# expansion_module_BT_RN42.net
KiCad netlist of a schematic drawn in EAGLE
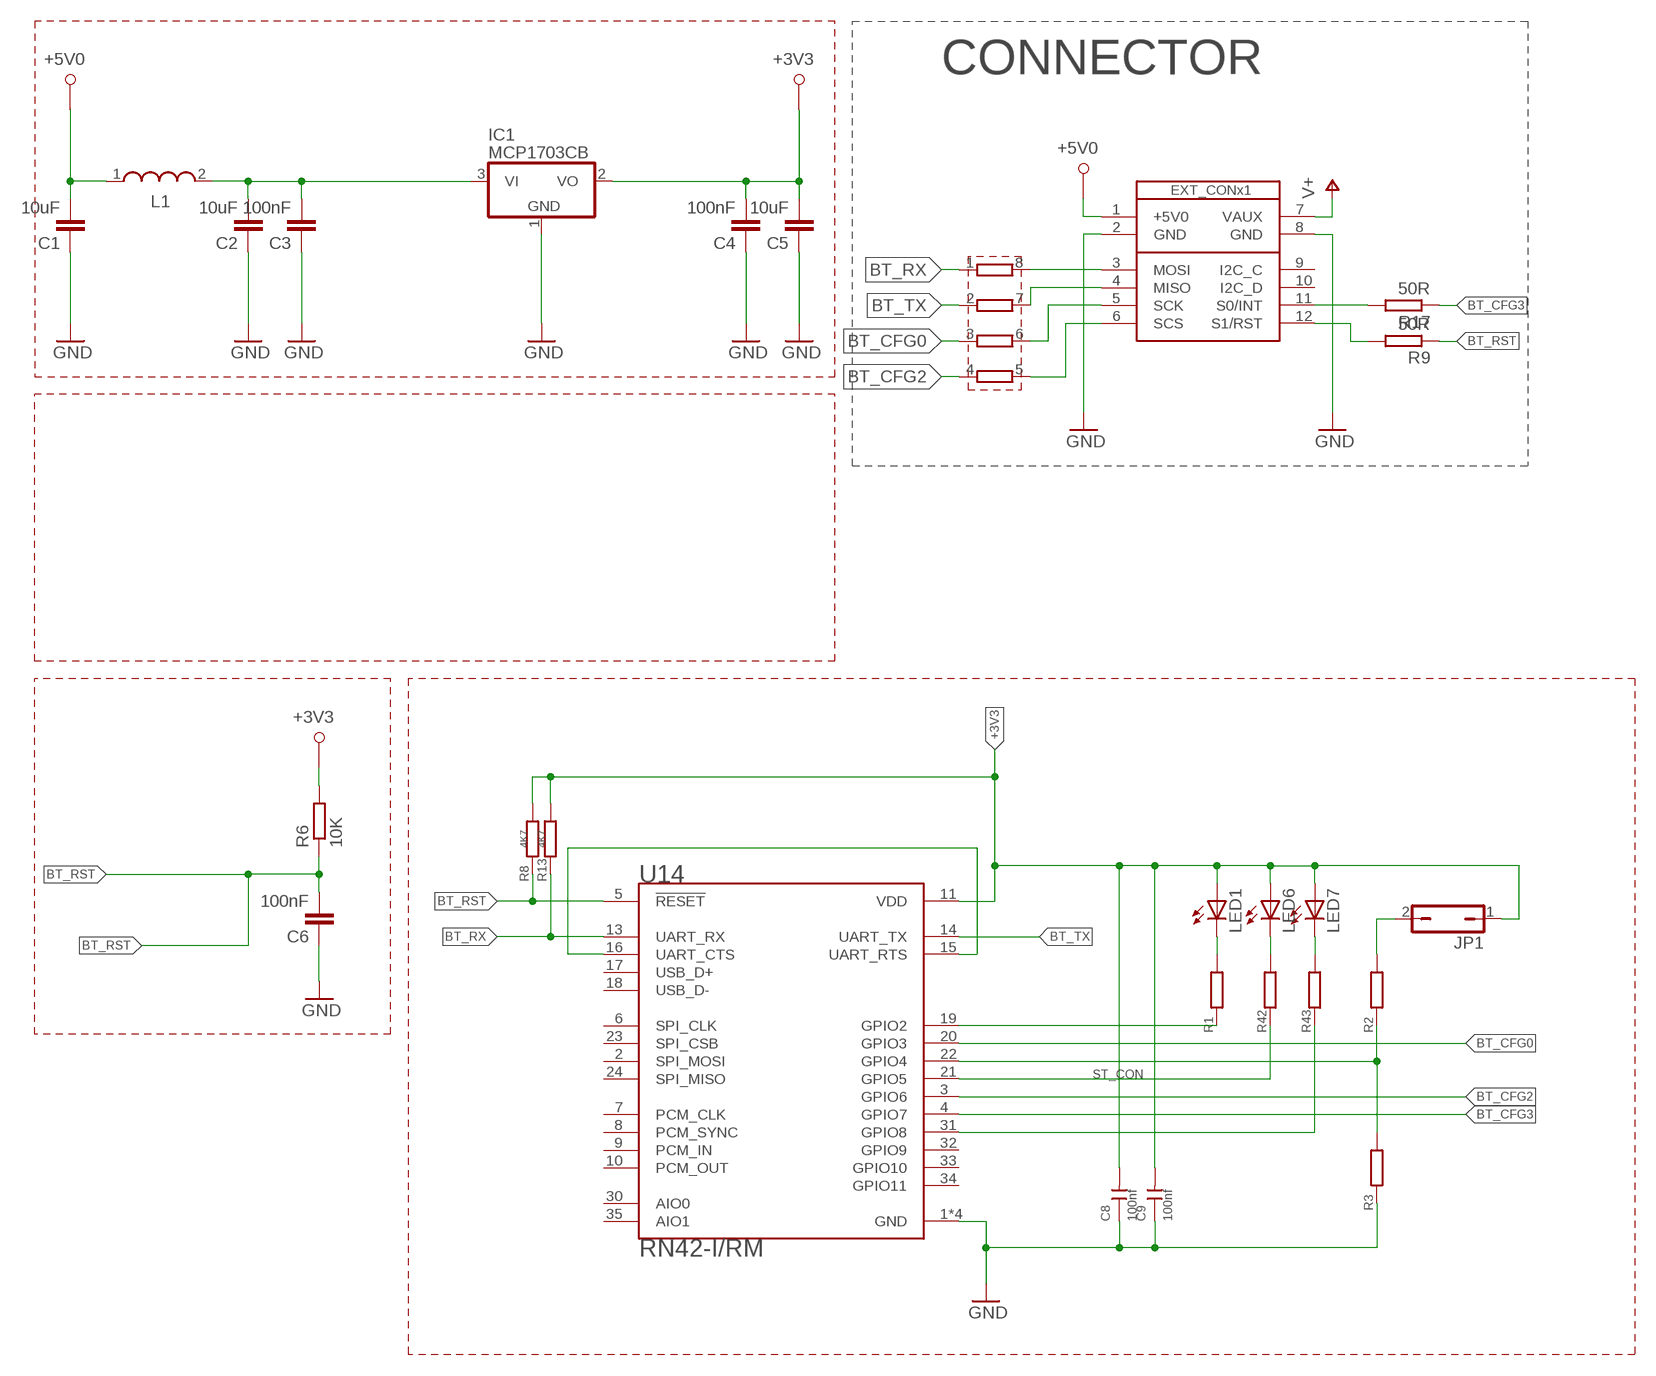
[diagram p0: schematic, sheet 1]

(export (version "E")
  (design (tool "Eeschema 10.0.6"))
  (components
    (comp (ref "C1")
      (value "10uF")
      (footprint "eagle-import:C0603")
      (libsource (lib "eagle-import") (part "C-EUC0603"))
    )
    (comp (ref "C2")
      (value "10uF")
      (footprint "eagle-import:C0603")
      (libsource (lib "eagle-import") (part "C-EUC0603"))
    )
    (comp (ref "C3")
      (value "100nF")
      (footprint "eagle-import:C0603")
      (libsource (lib "eagle-import") (part "C-EUC0603"))
    )
    (comp (ref "C4")
      (value "100nF")
      (footprint "eagle-import:C0603")
      (libsource (lib "eagle-import") (part "C-EUC0603"))
    )
    (comp (ref "C5")
      (value "10uF")
      (footprint "eagle-import:C0603")
      (libsource (lib "eagle-import") (part "C-EUC0603"))
    )
    (comp (ref "C6")
      (value "100nF")
      (footprint "eagle-import:C0402")
      (libsource (lib "eagle-import") (part "resistor_348_C-EUC0402"))
    )
    (comp (ref "C8")
      (value "100nf")
      (footprint "eagle-import:C0402")
      (fields (field (name "MPN") "CC0402KRX7R8BB104"))
      (libsource (lib "eagle-import") (part "CERAMIC-100NF-25V-10%-X7R(0402)"))
    )
    (comp (ref "C9")
      (value "100nf")
      (footprint "eagle-import:C0402")
      (fields (field (name "MPN") "CC0402KRX7R8BB104"))
      (libsource (lib "eagle-import") (part "CERAMIC-100NF-25V-10%-X7R(0402)"))
    )
    (comp (ref "IC1")
      (value "MCP1703CB")
      (footprint "eagle-import:SOT23")
      (libsource (lib "eagle-import") (part "MCP1703CB"))
    )
    (comp (ref "JP1")
      (value "JP1Q")
      (footprint "eagle-import:JP1")
      (libsource (lib "eagle-import") (part "JP1Q"))
    )
    (comp (ref "L1")
      (value "WE-LQ_1210")
      (footprint "eagle-import:WE-LQ_M")
      (libsource (lib "eagle-import") (part "WE-LQ_1210"))
    )
    (comp (ref "LED1")
      (value "LEDSML0603")
      (footprint "eagle-import:SML0603")
      (libsource (lib "eagle-import") (part "LEDSML0603"))
    )
    (comp (ref "LED6")
      (value "LEDSML0603")
      (footprint "eagle-import:SML0603")
      (libsource (lib "eagle-import") (part "LEDSML0603"))
    )
    (comp (ref "LED7")
      (value "LEDSML0603")
      (footprint "eagle-import:SML0603")
      (libsource (lib "eagle-import") (part "LEDSML0603"))
    )
    (comp (ref "R1")
      (value "RESISTOR_0402")
      (footprint "eagle-import:RESISITOR_0402")
      (libsource (lib "eagle-import") (part "RESISTOR_0402"))
    )
    (comp (ref "R2")
      (value "RESISTOR_0402")
      (footprint "eagle-import:RESISITOR_0402")
      (libsource (lib "eagle-import") (part "RESISTOR_0402"))
    )
    (comp (ref "R3")
      (value "RESISTOR_0402")
      (footprint "eagle-import:RESISITOR_0402")
      (libsource (lib "eagle-import") (part "RESISTOR_0402"))
    )
    (comp (ref "R6")
      (value "10K")
      (footprint "eagle-import:RESISITOR_0402")
      (libsource (lib "eagle-import") (part "RESISTOR_0402"))
    )
    (comp (ref "R8")
      (value "4K7")
      (footprint "eagle-import:RESISITOR_0402")
      (libsource (lib "eagle-import") (part "RESISTOR_0402"))
    )
    (comp (ref "R9")
      (value "50R")
      (footprint "eagle-import:RESISITOR_0402")
      (libsource (lib "eagle-import") (part "RESISTOR_0402"))
    )
    (comp (ref "R13")
      (value "4K7")
      (footprint "eagle-import:RESISITOR_0402")
      (libsource (lib "eagle-import") (part "RESISTOR_0402"))
    )
    (comp (ref "R17")
      (value "50R")
      (footprint "eagle-import:RESISITOR_0402")
      (libsource (lib "eagle-import") (part "RESISTOR_0402"))
    )
    (comp (ref "R42")
      (value "RESISTOR_0402")
      (footprint "eagle-import:RESISITOR_0402")
      (libsource (lib "eagle-import") (part "RESISTOR_0402"))
    )
    (comp (ref "R43")
      (value "RESISTOR_0402")
      (footprint "eagle-import:RESISITOR_0402")
      (libsource (lib "eagle-import") (part "RESISTOR_0402"))
    )
    (comp (ref "RN3")
      (value "RESISTOR-DIL_4R-N")
      (footprint "eagle-import:EXB28V")
      (libsource (lib "eagle-import") (part "RESISTOR-DIL_4R-N"))
    )
    (comp (ref "U$11")
      (value "SB_EXT_CON_X1_SPI")
      (footprint "eagle-import:SB_EXT_CON_X1_FULL")
      (libsource (lib "eagle-import") (part "SB_EXT_CON_X1_SPI"))
    )
    (comp (ref "U14")
      (value "RN42-I/RM")
      (footprint "eagle-import:XCVR_RN42-I_RM")
      (fields (field (name "MF") "Microchip"))
      (libsource (lib "eagle-import") (part "RN42-I/RM"))
    )
  )
  (nets
    (net (code "1") (name "+3V3") (class "Default")
      (node (ref "C4") (pin "2") (pinfunction "2_2") (pintype "passive"))
      (node (ref "C5") (pin "2") (pinfunction "2_2") (pintype "passive"))
      (node (ref "C8") (pin "2") (pinfunction "2_2") (pintype "passive"))
      (node (ref "C9") (pin "2") (pinfunction "2_2") (pintype "passive"))
      (node (ref "IC1") (pin "2") (pinfunction "VO_2") (pintype "passive"))
      (node (ref "JP1") (pin "1") (pinfunction "1_1") (pintype "passive"))
      (node (ref "LED1") (pin "A") (pinfunction "A_A") (pintype "passive"))
      (node (ref "LED6") (pin "A") (pinfunction "A_A") (pintype "passive"))
      (node (ref "LED7") (pin "A") (pinfunction "A_A") (pintype "passive"))
      (node (ref "R13") (pin "2") (pinfunction "2_2") (pintype "passive"))
      (node (ref "R6") (pin "2") (pinfunction "2_2") (pintype "passive"))
      (node (ref "R8") (pin "2") (pinfunction "2_2") (pintype "passive"))
      (node (ref "U14") (pin "11") (pinfunction "VDD_11") (pintype "power_in"))
    )
    (net (code "2") (name "+5V0") (class "Default")
      (node (ref "C1") (pin "2") (pinfunction "2_2") (pintype "passive"))
      (node (ref "L1") (pin "1") (pinfunction "1_1") (pintype "passive"))
      (node (ref "U$11") (pin "1") (pinfunction "+5V0_1") (pintype "bidirectional"))
    )
    (net (code "3") (name "/ST_CON") (class "Default")
      (node (ref "R42") (pin "1") (pinfunction "1_1") (pintype "passive"))
      (node (ref "U14") (pin "21") (pinfunction "GPIO5_21") (pintype "bidirectional"))
    )
    (net (code "4") (name "BT_CFG0") (class "Default")
      (node (ref "RN3") (pin "3") (pinfunction "3_3") (pintype "passive"))
      (node (ref "U14") (pin "20") (pinfunction "GPIO3_20") (pintype "bidirectional"))
    )
    (net (code "5") (name "BT_CFG2") (class "Default")
      (node (ref "RN3") (pin "4") (pinfunction "4_4") (pintype "passive"))
      (node (ref "U14") (pin "3") (pinfunction "GPIO6_3") (pintype "bidirectional"))
    )
    (net (code "6") (name "BT_CFG3") (class "Default")
      (node (ref "R17") (pin "1") (pinfunction "1_1") (pintype "passive"))
      (node (ref "U14") (pin "4") (pinfunction "GPIO7_4") (pintype "bidirectional"))
    )
    (net (code "7") (name "BT_RST") (class "Default")
      (node (ref "C6") (pin "2") (pinfunction "2_2") (pintype "passive"))
      (node (ref "R6") (pin "1") (pinfunction "1_1") (pintype "passive"))
      (node (ref "R8") (pin "1") (pinfunction "1_1") (pintype "passive"))
      (node (ref "R9") (pin "1") (pinfunction "1_1") (pintype "passive"))
      (node (ref "U14") (pin "5") (pinfunction "~{RESET}_5") (pintype "input"))
    )
    (net (code "8") (name "BT_RX") (class "Default")
      (node (ref "R13") (pin "1") (pinfunction "1_1") (pintype "passive"))
      (node (ref "RN3") (pin "1") (pinfunction "1_1") (pintype "passive"))
      (node (ref "U14") (pin "13") (pinfunction "UART_RX_13") (pintype "input"))
    )
    (net (code "9") (name "BT_TX") (class "Default")
      (node (ref "RN3") (pin "2") (pinfunction "2_2") (pintype "passive"))
      (node (ref "U14") (pin "14") (pinfunction "UART_TX_14") (pintype "output"))
    )
    (net (code "10") (name "GND") (class "Default")
      (node (ref "C1") (pin "1") (pinfunction "1_1") (pintype "passive"))
      (node (ref "C2") (pin "1") (pinfunction "1_1") (pintype "passive"))
      (node (ref "C3") (pin "1") (pinfunction "1_1") (pintype "passive"))
      (node (ref "C4") (pin "1") (pinfunction "1_1") (pintype "passive"))
      (node (ref "C5") (pin "1") (pinfunction "1_1") (pintype "passive"))
      (node (ref "C6") (pin "1") (pinfunction "1_1") (pintype "passive"))
      (node (ref "C8") (pin "1") (pinfunction "1_1") (pintype "passive"))
      (node (ref "C9") (pin "1") (pinfunction "1_1") (pintype "passive"))
      (node (ref "IC1") (pin "1") (pinfunction "GND_1") (pintype "passive"))
      (node (ref "R3") (pin "1") (pinfunction "1_1") (pintype "passive"))
      (node (ref "U$11") (pin "2") (pinfunction "GND_2") (pintype "bidirectional"))
      (node (ref "U$11") (pin "8") (pinfunction "GND_8") (pintype "bidirectional"))
      (node (ref "U14") (pin "1") (pinfunction "GND_1") (pintype "power_in"))
      (node (ref "U14") (pin "12") (pinfunction "GND_12") (pintype "power_in"))
      (node (ref "U14") (pin "28") (pinfunction "GND_28") (pintype "power_in"))
      (node (ref "U14") (pin "29") (pinfunction "GND_29") (pintype "power_in"))
    )
    (net (code "11") (name "Net-(IC1-VI)") (class "Default")
      (node (ref "C2") (pin "2") (pinfunction "2_2") (pintype "passive"))
      (node (ref "C3") (pin "2") (pinfunction "2_2") (pintype "passive"))
      (node (ref "IC1") (pin "3") (pinfunction "VI_3") (pintype "input"))
      (node (ref "L1") (pin "2") (pinfunction "2_2") (pintype "passive"))
    )
    (net (code "12") (name "Net-(JP1-Pad2)") (class "Default")
      (node (ref "JP1") (pin "2") (pinfunction "2_2") (pintype "passive"))
      (node (ref "R2") (pin "2") (pinfunction "2_2") (pintype "passive"))
    )
    (net (code "13") (name "Net-(LED1-PadC)") (class "Default")
      (node (ref "LED1") (pin "C") (pinfunction "C_C") (pintype "passive"))
      (node (ref "R1") (pin "2") (pinfunction "2_2") (pintype "passive"))
    )
    (net (code "14") (name "Net-(LED6-PadC)") (class "Default")
      (node (ref "LED6") (pin "C") (pinfunction "C_C") (pintype "passive"))
      (node (ref "R42") (pin "2") (pinfunction "2_2") (pintype "passive"))
    )
    (net (code "15") (name "Net-(LED7-PadC)") (class "Default")
      (node (ref "LED7") (pin "C") (pinfunction "C_C") (pintype "passive"))
      (node (ref "R43") (pin "2") (pinfunction "2_2") (pintype "passive"))
    )
    (net (code "16") (name "Net-(U$11-MISO)") (class "Default")
      (node (ref "RN3") (pin "7") (pinfunction "7_7") (pintype "passive"))
      (node (ref "U$11") (pin "4") (pinfunction "MISO_4") (pintype "bidirectional"))
    )
    (net (code "17") (name "Net-(U$11-MOSI)") (class "Default")
      (node (ref "RN3") (pin "8") (pinfunction "8_8") (pintype "passive"))
      (node (ref "U$11") (pin "3") (pinfunction "MOSI_3") (pintype "bidirectional"))
    )
    (net (code "18") (name "Net-(U$11-S0{slash}INT)") (class "Default")
      (node (ref "R17") (pin "2") (pinfunction "2_2") (pintype "passive"))
      (node (ref "U$11") (pin "11") (pinfunction "S0/INT_11") (pintype "bidirectional"))
    )
    (net (code "19") (name "Net-(U$11-S1{slash}RST)") (class "Default")
      (node (ref "R9") (pin "2") (pinfunction "2_2") (pintype "passive"))
      (node (ref "U$11") (pin "12") (pinfunction "S1/RST_12") (pintype "bidirectional"))
    )
    (net (code "20") (name "Net-(U$11-SCK)") (class "Default")
      (node (ref "RN3") (pin "6") (pinfunction "6_6") (pintype "passive"))
      (node (ref "U$11") (pin "5") (pinfunction "SCK_5") (pintype "bidirectional"))
    )
    (net (code "21") (name "Net-(U$11-SCS)") (class "Default")
      (node (ref "RN3") (pin "5") (pinfunction "5_5") (pintype "passive"))
      (node (ref "U$11") (pin "6") (pinfunction "SCS_6") (pintype "bidirectional"))
    )
    (net (code "22") (name "Net-(U14-GPIO2)") (class "Default")
      (node (ref "R1") (pin "1") (pinfunction "1_1") (pintype "passive"))
      (node (ref "U14") (pin "19") (pinfunction "GPIO2_19") (pintype "bidirectional"))
    )
    (net (code "23") (name "Net-(U14-GPIO4)") (class "Default")
      (node (ref "R2") (pin "1") (pinfunction "1_1") (pintype "passive"))
      (node (ref "R3") (pin "2") (pinfunction "2_2") (pintype "passive"))
      (node (ref "U14") (pin "22") (pinfunction "GPIO4_22") (pintype "bidirectional"))
    )
    (net (code "24") (name "Net-(U14-GPIO8)") (class "Default")
      (node (ref "R43") (pin "1") (pinfunction "1_1") (pintype "passive"))
      (node (ref "U14") (pin "31") (pinfunction "GPIO8_31") (pintype "bidirectional"))
    )
    (net (code "25") (name "Net-(U14-UART_CTS)") (class "Default")
      (node (ref "U14") (pin "15") (pinfunction "UART_RTS_15") (pintype "output"))
      (node (ref "U14") (pin "16") (pinfunction "UART_CTS_16") (pintype "input"))
    )
    (net (code "26") (name "V+") (class "Default")
      (node (ref "U$11") (pin "7") (pinfunction "VAUX_7") (pintype "bidirectional"))
    )
    (net (code "27") (name "unconnected-(U$11-I2C_C-Pad9)") (class "Default")
      (node (ref "U$11") (pin "9") (pinfunction "I2C_C_9") (pintype "bidirectional"))
    )
    (net (code "28") (name "unconnected-(U$11-I2C_D-Pad10)") (class "Default")
      (node (ref "U$11") (pin "10") (pinfunction "I2C_D_10") (pintype "bidirectional"))
    )
    (net (code "29") (name "unconnected-(U14-AIO0-Pad30)") (class "Default")
      (node (ref "U14") (pin "30") (pinfunction "AIO0_30") (pintype "bidirectional"))
    )
    (net (code "30") (name "unconnected-(U14-AIO1-Pad35)") (class "Default")
      (node (ref "U14") (pin "35") (pinfunction "AIO1_35") (pintype "bidirectional"))
    )
    (net (code "31") (name "unconnected-(U14-GPIO9-Pad32)") (class "Default")
      (node (ref "U14") (pin "32") (pinfunction "GPIO9_32") (pintype "bidirectional"))
    )
    (net (code "32") (name "unconnected-(U14-GPIO10-Pad33)") (class "Default")
      (node (ref "U14") (pin "33") (pinfunction "GPIO10_33") (pintype "bidirectional"))
    )
    (net (code "33") (name "unconnected-(U14-GPIO11-Pad34)") (class "Default")
      (node (ref "U14") (pin "34") (pinfunction "GPIO11_34") (pintype "bidirectional"))
    )
    (net (code "34") (name "unconnected-(U14-PCM_CLK-Pad7)") (class "Default")
      (node (ref "U14") (pin "7") (pinfunction "PCM_CLK_7") (pintype "bidirectional"))
    )
    (net (code "35") (name "unconnected-(U14-PCM_IN-Pad9)") (class "Default")
      (node (ref "U14") (pin "9") (pinfunction "PCM_IN_9") (pintype "input"))
    )
    (net (code "36") (name "unconnected-(U14-PCM_OUT-Pad10)") (class "Default")
      (node (ref "U14") (pin "10") (pinfunction "PCM_OUT_10") (pintype "output"))
    )
    (net (code "37") (name "unconnected-(U14-PCM_SYNC-Pad8)") (class "Default")
      (node (ref "U14") (pin "8") (pinfunction "PCM_SYNC_8") (pintype "bidirectional"))
    )
    (net (code "38") (name "unconnected-(U14-SPI_CLK-Pad6)") (class "Default")
      (node (ref "U14") (pin "6") (pinfunction "SPI_CLK_6") (pintype "input"))
    )
    (net (code "39") (name "unconnected-(U14-SPI_CSB-Pad23)") (class "Default")
      (node (ref "U14") (pin "23") (pinfunction "SPI_CSB_23") (pintype "input"))
    )
    (net (code "40") (name "unconnected-(U14-SPI_MISO-Pad24)") (class "Default")
      (node (ref "U14") (pin "24") (pinfunction "SPI_MISO_24") (pintype "output"))
    )
    (net (code "41") (name "unconnected-(U14-SPI_MOSI-Pad2)") (class "Default")
      (node (ref "U14") (pin "2") (pinfunction "SPI_MOSI_2") (pintype "input"))
    )
    (net (code "42") (name "unconnected-(U14-USB_D+-Pad17)") (class "Default")
      (node (ref "U14") (pin "17") (pinfunction "USB_D+_17") (pintype "bidirectional"))
    )
    (net (code "43") (name "unconnected-(U14-USB_D--Pad18)") (class "Default")
      (node (ref "U14") (pin "18") (pinfunction "USB_D-_18") (pintype "bidirectional"))
    )
  )
)
